# Ignitor_Outputs.net
KiCad netlist of a schematic drawn in Altium Designer
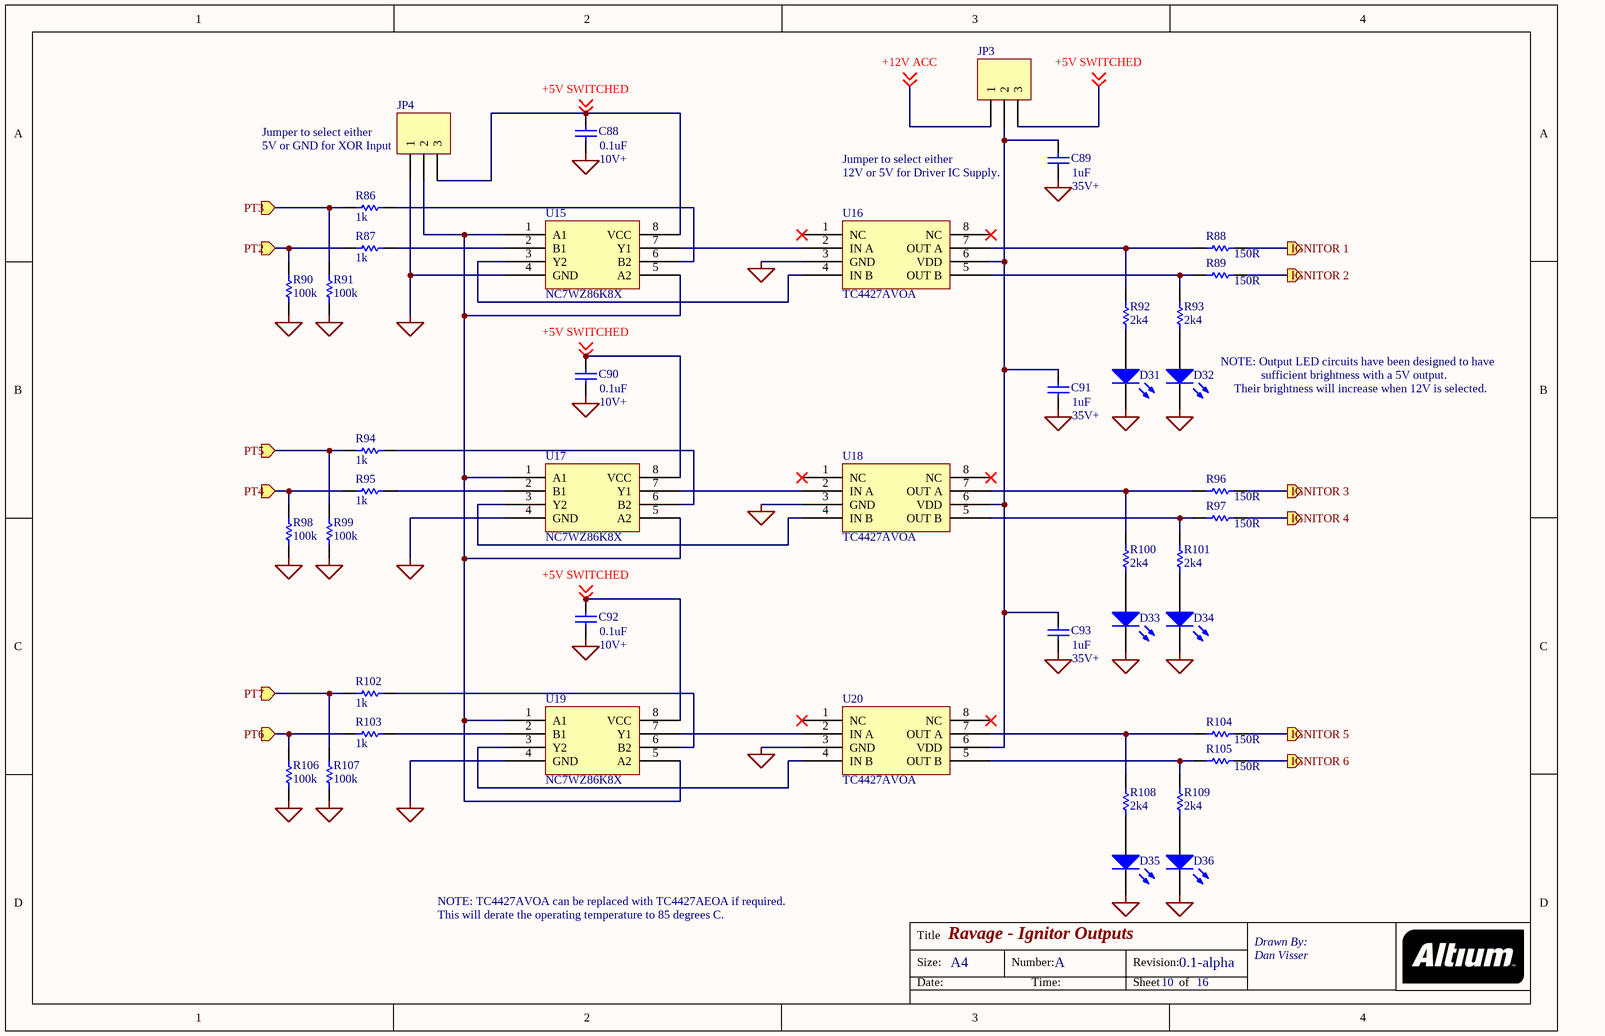
[diagram p0: Ignitor Outputs.SchDoc]

(export (version "E")
  (design (tool "Eeschema 10.0.6"))
  (components
    (comp (ref "C88")
      (value "0.1uF")
      (footprint "RAD-0.3")
      (description "Capacitor")
      (fields (field (name "PUBLISHER") "Altium Limited"))
      (libsource (lib "Miscellaneous Devices") (part "Cap"))
    )
    (comp (ref "C89")
      (value "1uF")
      (footprint "RAD-0.3")
      (description "Capacitor")
      (fields (field (name "PUBLISHER") "Altium Limited"))
      (libsource (lib "Miscellaneous Devices") (part "Cap"))
    )
    (comp (ref "C90")
      (value "0.1uF")
      (footprint "RAD-0.3")
      (description "Capacitor")
      (fields (field (name "PUBLISHER") "Altium Limited"))
      (libsource (lib "Miscellaneous Devices") (part "Cap"))
    )
    (comp (ref "C91")
      (value "1uF")
      (footprint "RAD-0.3")
      (description "Capacitor")
      (fields (field (name "PUBLISHER") "Altium Limited"))
      (libsource (lib "Miscellaneous Devices") (part "Cap"))
    )
    (comp (ref "C92")
      (value "0.1uF")
      (footprint "RAD-0.3")
      (description "Capacitor")
      (fields (field (name "PUBLISHER") "Altium Limited"))
      (libsource (lib "Miscellaneous Devices") (part "Cap"))
    )
    (comp (ref "C93")
      (value "1uF")
      (footprint "RAD-0.3")
      (description "Capacitor")
      (fields (field (name "PUBLISHER") "Altium Limited"))
      (libsource (lib "Miscellaneous Devices") (part "Cap"))
    )
    (comp (ref "D31")
      (value "~")
      (footprint "LED-0")
      (description "Typical INFRARED GaAs LED")
      (fields (field (name "PUBLISHER") "Altium Limited"))
      (libsource (lib "Miscellaneous Devices") (part "LED0"))
    )
    (comp (ref "D32")
      (value "~")
      (footprint "LED-0")
      (description "Typical INFRARED GaAs LED")
      (fields (field (name "PUBLISHER") "Altium Limited"))
      (libsource (lib "Miscellaneous Devices") (part "LED0"))
    )
    (comp (ref "D33")
      (value "~")
      (footprint "LED-0")
      (description "Typical INFRARED GaAs LED")
      (fields (field (name "PUBLISHER") "Altium Limited"))
      (libsource (lib "Miscellaneous Devices") (part "LED0"))
    )
    (comp (ref "D34")
      (value "~")
      (footprint "LED-0")
      (description "Typical INFRARED GaAs LED")
      (fields (field (name "PUBLISHER") "Altium Limited"))
      (libsource (lib "Miscellaneous Devices") (part "LED0"))
    )
    (comp (ref "D35")
      (value "~")
      (footprint "LED-0")
      (description "Typical INFRARED GaAs LED")
      (fields (field (name "PUBLISHER") "Altium Limited"))
      (libsource (lib "Miscellaneous Devices") (part "LED0"))
    )
    (comp (ref "D36")
      (value "~")
      (footprint "LED-0")
      (description "Typical INFRARED GaAs LED")
      (fields (field (name "PUBLISHER") "Altium Limited"))
      (libsource (lib "Miscellaneous Devices") (part "LED0"))
    )
    (comp (ref "JP3")
      (value "~")
      (footprint "HDR1X3")
      (description "Header, 3-Pin")
      (fields (field (name "PUBLISHER") "Altium Limited"))
      (libsource (lib "Miscellaneous Connectors") (part "Header 3"))
    )
    (comp (ref "JP4")
      (value "~")
      (footprint "HDR1X3")
      (description "Header, 3-Pin")
      (fields (field (name "PUBLISHER") "Altium Limited"))
      (libsource (lib "Miscellaneous Connectors") (part "Header 3"))
    )
    (comp (ref "R86")
      (value "1k")
      (footprint "AXIAL-0.3")
      (description "Resistor")
      (fields (field (name "PUBLISHER") "Altium Limited"))
      (libsource (lib "Miscellaneous Devices") (part "Res1"))
    )
    (comp (ref "R87")
      (value "1k")
      (footprint "AXIAL-0.3")
      (description "Resistor")
      (fields (field (name "PUBLISHER") "Altium Limited"))
      (libsource (lib "Miscellaneous Devices") (part "Res1"))
    )
    (comp (ref "R88")
      (value "150R")
      (footprint "AXIAL-0.3")
      (description "Resistor")
      (fields (field (name "PUBLISHER") "Altium Limited"))
      (libsource (lib "Miscellaneous Devices") (part "Res1"))
    )
    (comp (ref "R89")
      (value "150R")
      (footprint "AXIAL-0.3")
      (description "Resistor")
      (fields (field (name "PUBLISHER") "Altium Limited"))
      (libsource (lib "Miscellaneous Devices") (part "Res1"))
    )
    (comp (ref "R90")
      (value "100k")
      (footprint "AXIAL-0.3")
      (description "Resistor")
      (fields (field (name "PUBLISHER") "Altium Limited"))
      (libsource (lib "Miscellaneous Devices") (part "Res1"))
    )
    (comp (ref "R91")
      (value "100k")
      (footprint "AXIAL-0.3")
      (description "Resistor")
      (fields (field (name "PUBLISHER") "Altium Limited"))
      (libsource (lib "Miscellaneous Devices") (part "Res1"))
    )
    (comp (ref "R92")
      (value "2k4")
      (footprint "AXIAL-0.3")
      (description "Resistor")
      (fields (field (name "PUBLISHER") "Altium Limited"))
      (libsource (lib "Miscellaneous Devices") (part "Res1"))
    )
    (comp (ref "R93")
      (value "2k4")
      (footprint "AXIAL-0.3")
      (description "Resistor")
      (fields (field (name "PUBLISHER") "Altium Limited"))
      (libsource (lib "Miscellaneous Devices") (part "Res1"))
    )
    (comp (ref "R94")
      (value "1k")
      (footprint "AXIAL-0.3")
      (description "Resistor")
      (fields (field (name "PUBLISHER") "Altium Limited"))
      (libsource (lib "Miscellaneous Devices") (part "Res1"))
    )
    (comp (ref "R95")
      (value "1k")
      (footprint "AXIAL-0.3")
      (description "Resistor")
      (fields (field (name "PUBLISHER") "Altium Limited"))
      (libsource (lib "Miscellaneous Devices") (part "Res1"))
    )
    (comp (ref "R96")
      (value "150R")
      (footprint "AXIAL-0.3")
      (description "Resistor")
      (fields (field (name "PUBLISHER") "Altium Limited"))
      (libsource (lib "Miscellaneous Devices") (part "Res1"))
    )
    (comp (ref "R97")
      (value "150R")
      (footprint "AXIAL-0.3")
      (description "Resistor")
      (fields (field (name "PUBLISHER") "Altium Limited"))
      (libsource (lib "Miscellaneous Devices") (part "Res1"))
    )
    (comp (ref "R98")
      (value "100k")
      (footprint "AXIAL-0.3")
      (description "Resistor")
      (fields (field (name "PUBLISHER") "Altium Limited"))
      (libsource (lib "Miscellaneous Devices") (part "Res1"))
    )
    (comp (ref "R99")
      (value "100k")
      (footprint "AXIAL-0.3")
      (description "Resistor")
      (fields (field (name "PUBLISHER") "Altium Limited"))
      (libsource (lib "Miscellaneous Devices") (part "Res1"))
    )
    (comp (ref "R100")
      (value "2k4")
      (footprint "AXIAL-0.3")
      (description "Resistor")
      (fields (field (name "PUBLISHER") "Altium Limited"))
      (libsource (lib "Miscellaneous Devices") (part "Res1"))
    )
    (comp (ref "R101")
      (value "2k4")
      (footprint "AXIAL-0.3")
      (description "Resistor")
      (fields (field (name "PUBLISHER") "Altium Limited"))
      (libsource (lib "Miscellaneous Devices") (part "Res1"))
    )
    (comp (ref "R102")
      (value "1k")
      (footprint "AXIAL-0.3")
      (description "Resistor")
      (fields (field (name "PUBLISHER") "Altium Limited"))
      (libsource (lib "Miscellaneous Devices") (part "Res1"))
    )
    (comp (ref "R103")
      (value "1k")
      (footprint "AXIAL-0.3")
      (description "Resistor")
      (fields (field (name "PUBLISHER") "Altium Limited"))
      (libsource (lib "Miscellaneous Devices") (part "Res1"))
    )
    (comp (ref "R104")
      (value "150R")
      (footprint "AXIAL-0.3")
      (description "Resistor")
      (fields (field (name "PUBLISHER") "Altium Limited"))
      (libsource (lib "Miscellaneous Devices") (part "Res1"))
    )
    (comp (ref "R105")
      (value "150R")
      (footprint "AXIAL-0.3")
      (description "Resistor")
      (fields (field (name "PUBLISHER") "Altium Limited"))
      (libsource (lib "Miscellaneous Devices") (part "Res1"))
    )
    (comp (ref "R106")
      (value "100k")
      (footprint "AXIAL-0.3")
      (description "Resistor")
      (fields (field (name "PUBLISHER") "Altium Limited"))
      (libsource (lib "Miscellaneous Devices") (part "Res1"))
    )
    (comp (ref "R107")
      (value "100k")
      (footprint "AXIAL-0.3")
      (description "Resistor")
      (fields (field (name "PUBLISHER") "Altium Limited"))
      (libsource (lib "Miscellaneous Devices") (part "Res1"))
    )
    (comp (ref "R108")
      (value "2k4")
      (footprint "AXIAL-0.3")
      (description "Resistor")
      (fields (field (name "PUBLISHER") "Altium Limited"))
      (libsource (lib "Miscellaneous Devices") (part "Res1"))
    )
    (comp (ref "R109")
      (value "2k4")
      (footprint "AXIAL-0.3")
      (description "Resistor")
      (fields (field (name "PUBLISHER") "Altium Limited"))
      (libsource (lib "Miscellaneous Devices") (part "Res1"))
    )
    (comp (ref "U15") (value "NC7WZ86K8X") (libsource (lib "FreeEMS Schematic Library") (part "NC7WZ86K8X")))
    (comp (ref "U16") (value "TC4427AVOA") (libsource (lib "FreeEMS Schematic Library") (part "TC427COA")))
    (comp (ref "U17") (value "NC7WZ86K8X") (libsource (lib "FreeEMS Schematic Library") (part "NC7WZ86K8X")))
    (comp (ref "U18") (value "TC4427AVOA") (libsource (lib "FreeEMS Schematic Library") (part "TC427COA")))
    (comp (ref "U19") (value "NC7WZ86K8X") (libsource (lib "FreeEMS Schematic Library") (part "NC7WZ86K8X")))
    (comp (ref "U20") (value "TC4427AVOA") (libsource (lib "FreeEMS Schematic Library") (part "TC427COA")))
  )
  (nets
    (net (code "1") (name "+5V SWITCHED") (class "Default")
      (node (ref "C88") (pin "2") (pinfunction "2_2") (pintype "passive"))
      (node (ref "C90") (pin "2") (pinfunction "2_2") (pintype "passive"))
      (node (ref "C92") (pin "2") (pinfunction "2_2") (pintype "passive"))
      (node (ref "JP3") (pin "3") (pinfunction "3_3") (pintype "passive"))
      (node (ref "JP4") (pin "3") (pinfunction "3_3") (pintype "passive"))
      (node (ref "U15") (pin "8") (pinfunction "VCC_8") (pintype "passive"))
      (node (ref "U17") (pin "8") (pinfunction "VCC_8") (pintype "passive"))
      (node (ref "U19") (pin "8") (pinfunction "VCC_8") (pintype "passive"))
    )
    (net (code "2") (name "+12V ACC") (class "Default")
      (node (ref "JP3") (pin "1") (pinfunction "1_1") (pintype "passive"))
    )
    (net (code "3") (name "/IGNITOR 1") (class "Default")
      (node (ref "R88") (pin "2") (pinfunction "2_2") (pintype "passive"))
    )
    (net (code "4") (name "/IGNITOR 2") (class "Default")
      (node (ref "R89") (pin "2") (pinfunction "2_2") (pintype "passive"))
    )
    (net (code "5") (name "/IGNITOR 3") (class "Default")
      (node (ref "R96") (pin "2") (pinfunction "2_2") (pintype "passive"))
    )
    (net (code "6") (name "/IGNITOR 4") (class "Default")
      (node (ref "R97") (pin "2") (pinfunction "2_2") (pintype "passive"))
    )
    (net (code "7") (name "/IGNITOR 5") (class "Default")
      (node (ref "R104") (pin "2") (pinfunction "2_2") (pintype "passive"))
    )
    (net (code "8") (name "/IGNITOR 6") (class "Default")
      (node (ref "R105") (pin "2") (pinfunction "2_2") (pintype "passive"))
    )
    (net (code "9") (name "/PT2") (class "Default")
      (node (ref "R87") (pin "2") (pinfunction "2_2") (pintype "passive"))
      (node (ref "R90") (pin "2") (pinfunction "2_2") (pintype "passive"))
    )
    (net (code "10") (name "/PT3") (class "Default")
      (node (ref "R86") (pin "2") (pinfunction "2_2") (pintype "passive"))
      (node (ref "R91") (pin "2") (pinfunction "2_2") (pintype "passive"))
    )
    (net (code "11") (name "/PT4") (class "Default")
      (node (ref "R95") (pin "2") (pinfunction "2_2") (pintype "passive"))
      (node (ref "R98") (pin "2") (pinfunction "2_2") (pintype "passive"))
    )
    (net (code "12") (name "/PT5") (class "Default")
      (node (ref "R94") (pin "2") (pinfunction "2_2") (pintype "passive"))
      (node (ref "R99") (pin "2") (pinfunction "2_2") (pintype "passive"))
    )
    (net (code "13") (name "/PT6") (class "Default")
      (node (ref "R103") (pin "2") (pinfunction "2_2") (pintype "passive"))
      (node (ref "R106") (pin "2") (pinfunction "2_2") (pintype "passive"))
    )
    (net (code "14") (name "/PT7") (class "Default")
      (node (ref "R102") (pin "2") (pinfunction "2_2") (pintype "passive"))
      (node (ref "R107") (pin "2") (pinfunction "2_2") (pintype "passive"))
    )
    (net (code "15") (name "<NO NET>") (class "Default")
      (node (ref "C88") (pin "1") (pinfunction "1_1") (pintype "passive"))
      (node (ref "C89") (pin "1") (pinfunction "1_1") (pintype "passive"))
      (node (ref "C90") (pin "1") (pinfunction "1_1") (pintype "passive"))
      (node (ref "C91") (pin "1") (pinfunction "1_1") (pintype "passive"))
      (node (ref "C92") (pin "1") (pinfunction "1_1") (pintype "passive"))
      (node (ref "C93") (pin "1") (pinfunction "1_1") (pintype "passive"))
      (node (ref "D31") (pin "2") (pinfunction "K_2") (pintype "passive"))
      (node (ref "D32") (pin "2") (pinfunction "K_2") (pintype "passive"))
      (node (ref "D33") (pin "2") (pinfunction "K_2") (pintype "passive"))
      (node (ref "D34") (pin "2") (pinfunction "K_2") (pintype "passive"))
      (node (ref "D35") (pin "2") (pinfunction "K_2") (pintype "passive"))
      (node (ref "D36") (pin "2") (pinfunction "K_2") (pintype "passive"))
      (node (ref "JP4") (pin "1") (pinfunction "1_1") (pintype "passive"))
      (node (ref "R106") (pin "1") (pinfunction "1_1") (pintype "passive"))
      (node (ref "R107") (pin "1") (pinfunction "1_1") (pintype "passive"))
      (node (ref "R90") (pin "1") (pinfunction "1_1") (pintype "passive"))
      (node (ref "R91") (pin "1") (pinfunction "1_1") (pintype "passive"))
      (node (ref "R98") (pin "1") (pinfunction "1_1") (pintype "passive"))
      (node (ref "R99") (pin "1") (pinfunction "1_1") (pintype "passive"))
      (node (ref "U15") (pin "4") (pinfunction "GND_4") (pintype "passive"))
      (node (ref "U16") (pin "3") (pinfunction "GND_3") (pintype "passive"))
      (node (ref "U17") (pin "4") (pinfunction "GND_4") (pintype "passive"))
      (node (ref "U18") (pin "3") (pinfunction "GND_3") (pintype "passive"))
      (node (ref "U19") (pin "4") (pinfunction "GND_4") (pintype "passive"))
      (node (ref "U20") (pin "3") (pinfunction "GND_3") (pintype "passive"))
    )
    (net (code "16") (name "Net-(D31-A)") (class "Default")
      (node (ref "D31") (pin "1") (pinfunction "A_1") (pintype "passive"))
      (node (ref "R92") (pin "1") (pinfunction "1_1") (pintype "passive"))
    )
    (net (code "17") (name "Net-(D32-A)") (class "Default")
      (node (ref "D32") (pin "1") (pinfunction "A_1") (pintype "passive"))
      (node (ref "R93") (pin "1") (pinfunction "1_1") (pintype "passive"))
    )
    (net (code "18") (name "Net-(D33-A)") (class "Default")
      (node (ref "D33") (pin "1") (pinfunction "A_1") (pintype "passive"))
      (node (ref "R100") (pin "1") (pinfunction "1_1") (pintype "passive"))
    )
    (net (code "19") (name "Net-(D34-A)") (class "Default")
      (node (ref "D34") (pin "1") (pinfunction "A_1") (pintype "passive"))
      (node (ref "R101") (pin "1") (pinfunction "1_1") (pintype "passive"))
    )
    (net (code "20") (name "Net-(D35-A)") (class "Default")
      (node (ref "D35") (pin "1") (pinfunction "A_1") (pintype "passive"))
      (node (ref "R108") (pin "1") (pinfunction "1_1") (pintype "passive"))
    )
    (net (code "21") (name "Net-(D36-A)") (class "Default")
      (node (ref "D36") (pin "1") (pinfunction "A_1") (pintype "passive"))
      (node (ref "R109") (pin "1") (pinfunction "1_1") (pintype "passive"))
    )
    (net (code "22") (name "Net-(U15-A1)") (class "Default")
      (node (ref "JP4") (pin "2") (pinfunction "2_2") (pintype "passive"))
      (node (ref "U15") (pin "1") (pinfunction "A1_1") (pintype "passive"))
      (node (ref "U15") (pin "5") (pinfunction "A2_5") (pintype "passive"))
      (node (ref "U17") (pin "1") (pinfunction "A1_1") (pintype "passive"))
      (node (ref "U17") (pin "5") (pinfunction "A2_5") (pintype "passive"))
      (node (ref "U19") (pin "1") (pinfunction "A1_1") (pintype "passive"))
      (node (ref "U19") (pin "5") (pinfunction "A2_5") (pintype "passive"))
    )
    (net (code "23") (name "Net-(U15-B1)") (class "Default")
      (node (ref "R87") (pin "1") (pinfunction "1_1") (pintype "passive"))
      (node (ref "U15") (pin "2") (pinfunction "B1_2") (pintype "passive"))
    )
    (net (code "24") (name "Net-(U15-B2)") (class "Default")
      (node (ref "R86") (pin "1") (pinfunction "1_1") (pintype "passive"))
      (node (ref "U15") (pin "6") (pinfunction "B2_6") (pintype "passive"))
    )
    (net (code "25") (name "Net-(U15-Y1)") (class "Default")
      (node (ref "U15") (pin "7") (pinfunction "Y1_7") (pintype "passive"))
      (node (ref "U16") (pin "2") (pinfunction "IN_A_2") (pintype "passive"))
    )
    (net (code "26") (name "Net-(U15-Y2)") (class "Default")
      (node (ref "U15") (pin "3") (pinfunction "Y2_3") (pintype "passive"))
      (node (ref "U16") (pin "4") (pinfunction "IN_B_4") (pintype "passive"))
    )
    (net (code "27") (name "Net-(U16-OUT_A)") (class "Default")
      (node (ref "R88") (pin "1") (pinfunction "1_1") (pintype "passive"))
      (node (ref "R92") (pin "2") (pinfunction "2_2") (pintype "passive"))
      (node (ref "U16") (pin "7") (pinfunction "OUT_A_7") (pintype "passive"))
    )
    (net (code "28") (name "Net-(U16-OUT_B)") (class "Default")
      (node (ref "R89") (pin "1") (pinfunction "1_1") (pintype "passive"))
      (node (ref "R93") (pin "2") (pinfunction "2_2") (pintype "passive"))
      (node (ref "U16") (pin "5") (pinfunction "OUT_B_5") (pintype "passive"))
    )
    (net (code "29") (name "Net-(U16-VDD)") (class "Default")
      (node (ref "C89") (pin "2") (pinfunction "2_2") (pintype "passive"))
      (node (ref "C91") (pin "2") (pinfunction "2_2") (pintype "passive"))
      (node (ref "C93") (pin "2") (pinfunction "2_2") (pintype "passive"))
      (node (ref "JP3") (pin "2") (pinfunction "2_2") (pintype "passive"))
      (node (ref "U16") (pin "6") (pinfunction "VDD_6") (pintype "passive"))
      (node (ref "U18") (pin "6") (pinfunction "VDD_6") (pintype "passive"))
      (node (ref "U20") (pin "6") (pinfunction "VDD_6") (pintype "passive"))
    )
    (net (code "30") (name "Net-(U17-B1)") (class "Default")
      (node (ref "R95") (pin "1") (pinfunction "1_1") (pintype "passive"))
      (node (ref "U17") (pin "2") (pinfunction "B1_2") (pintype "passive"))
    )
    (net (code "31") (name "Net-(U17-B2)") (class "Default")
      (node (ref "R94") (pin "1") (pinfunction "1_1") (pintype "passive"))
      (node (ref "U17") (pin "6") (pinfunction "B2_6") (pintype "passive"))
    )
    (net (code "32") (name "Net-(U17-Y1)") (class "Default")
      (node (ref "U17") (pin "7") (pinfunction "Y1_7") (pintype "passive"))
      (node (ref "U18") (pin "2") (pinfunction "IN_A_2") (pintype "passive"))
    )
    (net (code "33") (name "Net-(U17-Y2)") (class "Default")
      (node (ref "U17") (pin "3") (pinfunction "Y2_3") (pintype "passive"))
      (node (ref "U18") (pin "4") (pinfunction "IN_B_4") (pintype "passive"))
    )
    (net (code "34") (name "Net-(U18-OUT_A)") (class "Default")
      (node (ref "R100") (pin "2") (pinfunction "2_2") (pintype "passive"))
      (node (ref "R96") (pin "1") (pinfunction "1_1") (pintype "passive"))
      (node (ref "U18") (pin "7") (pinfunction "OUT_A_7") (pintype "passive"))
    )
    (net (code "35") (name "Net-(U18-OUT_B)") (class "Default")
      (node (ref "R101") (pin "2") (pinfunction "2_2") (pintype "passive"))
      (node (ref "R97") (pin "1") (pinfunction "1_1") (pintype "passive"))
      (node (ref "U18") (pin "5") (pinfunction "OUT_B_5") (pintype "passive"))
    )
    (net (code "36") (name "Net-(U19-B1)") (class "Default")
      (node (ref "R103") (pin "1") (pinfunction "1_1") (pintype "passive"))
      (node (ref "U19") (pin "2") (pinfunction "B1_2") (pintype "passive"))
    )
    (net (code "37") (name "Net-(U19-B2)") (class "Default")
      (node (ref "R102") (pin "1") (pinfunction "1_1") (pintype "passive"))
      (node (ref "U19") (pin "6") (pinfunction "B2_6") (pintype "passive"))
    )
    (net (code "38") (name "Net-(U19-Y1)") (class "Default")
      (node (ref "U19") (pin "7") (pinfunction "Y1_7") (pintype "passive"))
      (node (ref "U20") (pin "2") (pinfunction "IN_A_2") (pintype "passive"))
    )
    (net (code "39") (name "Net-(U19-Y2)") (class "Default")
      (node (ref "U19") (pin "3") (pinfunction "Y2_3") (pintype "passive"))
      (node (ref "U20") (pin "4") (pinfunction "IN_B_4") (pintype "passive"))
    )
    (net (code "40") (name "Net-(U20-OUT_A)") (class "Default")
      (node (ref "R104") (pin "1") (pinfunction "1_1") (pintype "passive"))
      (node (ref "R108") (pin "2") (pinfunction "2_2") (pintype "passive"))
      (node (ref "U20") (pin "7") (pinfunction "OUT_A_7") (pintype "passive"))
    )
    (net (code "41") (name "Net-(U20-OUT_B)") (class "Default")
      (node (ref "R105") (pin "1") (pinfunction "1_1") (pintype "passive"))
      (node (ref "R109") (pin "2") (pinfunction "2_2") (pintype "passive"))
      (node (ref "U20") (pin "5") (pinfunction "OUT_B_5") (pintype "passive"))
    )
    (net (code "42") (name "unconnected-(U16-NC-Pad1)") (class "Default")
      (node (ref "U16") (pin "1") (pinfunction "NC_1") (pintype "passive+no_connect"))
    )
    (net (code "43") (name "unconnected-(U16-NC-Pad8)") (class "Default")
      (node (ref "U16") (pin "8") (pinfunction "NC_8") (pintype "passive+no_connect"))
    )
    (net (code "44") (name "unconnected-(U18-NC-Pad1)") (class "Default")
      (node (ref "U18") (pin "1") (pinfunction "NC_1") (pintype "passive+no_connect"))
    )
    (net (code "45") (name "unconnected-(U18-NC-Pad8)") (class "Default")
      (node (ref "U18") (pin "8") (pinfunction "NC_8") (pintype "passive+no_connect"))
    )
    (net (code "46") (name "unconnected-(U20-NC-Pad1)") (class "Default")
      (node (ref "U20") (pin "1") (pinfunction "NC_1") (pintype "passive+no_connect"))
    )
    (net (code "47") (name "unconnected-(U20-NC-Pad8)") (class "Default")
      (node (ref "U20") (pin "8") (pinfunction "NC_8") (pintype "passive+no_connect"))
    )
  )
)
